# USB_POWER.net
KiCad netlist of a schematic drawn in Altium Designer
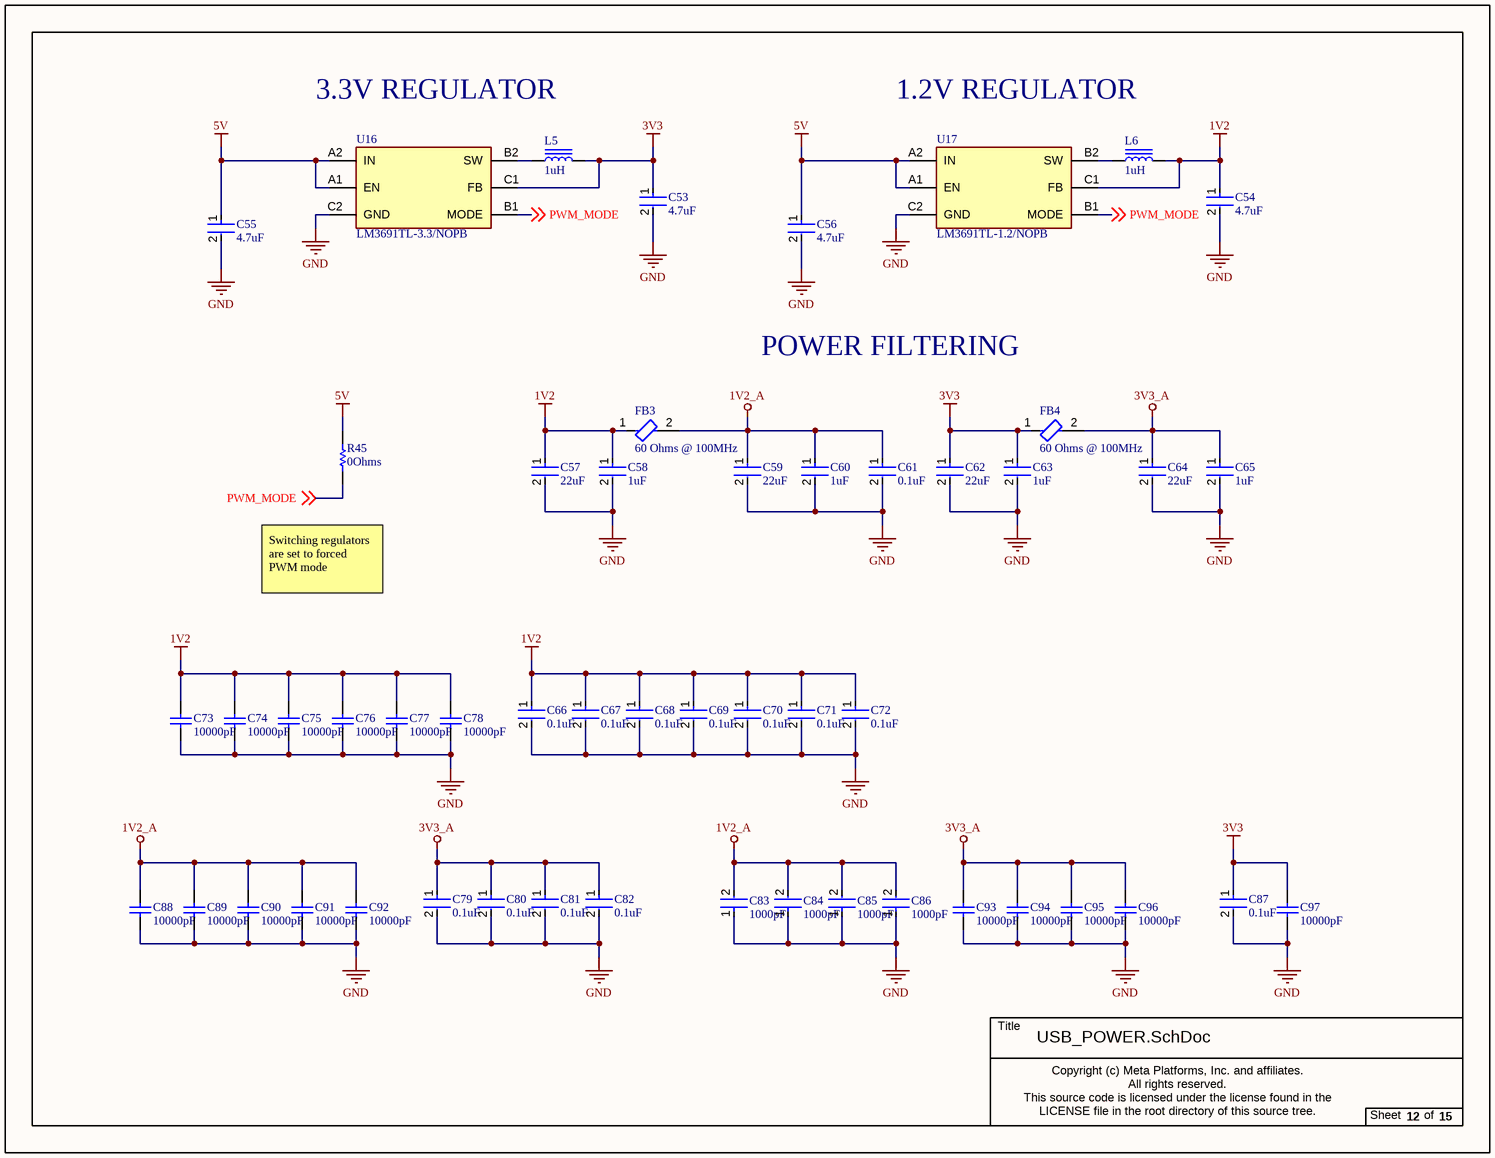
[diagram p0: USB_POWER.SchDoc]

(export (version "E")
  (design (tool "Eeschema 10.0.6"))
  (components
    (comp (ref "C53")
      (value "4.7uF")
      (footprint "FP-CL828-IPC_C")
      (description "Cap Ceramic 4.7uF 10V X5R ±10% SMD 0402 +85°C Paper T/R")
      (fields (field (name "TOLERANCE") "10%"))
      (libsource (lib "Altium Content Vault") (part "b4654b650e69147ec39a6b967a45e02"))
    )
    (comp (ref "C54")
      (value "4.7uF")
      (footprint "FP-CL828-IPC_C")
      (description "Cap Ceramic 4.7uF 10V X5R ±10% SMD 0402 +85°C Paper T/R")
      (fields (field (name "TOLERANCE") "10%"))
      (libsource (lib "Altium Content Vault") (part "b4654b650e69147ec39a6b967a45e02"))
    )
    (comp (ref "C55")
      (value "4.7uF")
      (footprint "FP-CL828-IPC_C")
      (description "Cap Ceramic 4.7uF 10V X5R ±10% SMD 0402 +85°C Paper T/R")
      (fields (field (name "TOLERANCE") "10%"))
      (libsource (lib "Altium Content Vault") (part "b4654b650e69147ec39a6b967a45e02"))
    )
    (comp (ref "C56")
      (value "4.7uF")
      (footprint "FP-CL828-IPC_C")
      (description "Cap Ceramic 4.7uF 10V X5R ±10% SMD 0402 +85°C Paper T/R")
      (fields (field (name "TOLERANCE") "10%"))
      (libsource (lib "Altium Content Vault") (part "b4654b650e69147ec39a6b967a45e02"))
    )
    (comp (ref "C57")
      (value "22uF")
      (footprint "FP-CL05A226MQ5N6J8-IPC_C")
      (description "CAP CER 22UF 6.3V X5R 0402")
      (fields
        (field (name "MANUFACTURER PART NUMBER") "CL05A226MQ5N6J8")
        (field (name "MANUFACTURER") "Samsung Electro-Mechanics")
      )
      (libsource (lib "Altium Content Vault") (part "11868f565c42a9108669ba33697ecf6"))
    )
    (comp (ref "C58")
      (value "1uF")
      (footprint "FP-CL511-IPC_C")
      (description "Cap Ceramic 1uF 10V X5R ±10% SMD 0402 +85°C Paper T/R")
      (fields (field (name "TOLERANCE") "10%"))
      (libsource (lib "Altium Content Vault") (part "b4654b650e69147ec39a6b967a45e02"))
    )
    (comp (ref "C59")
      (value "22uF")
      (footprint "FP-CL05A226MQ5N6J8-IPC_C")
      (description "CAP CER 22UF 6.3V X5R 0402")
      (fields
        (field (name "MANUFACTURER PART NUMBER") "CL05A226MQ5N6J8")
        (field (name "MANUFACTURER") "Samsung Electro-Mechanics")
      )
      (libsource (lib "Altium Content Vault") (part "11868f565c42a9108669ba33697ecf6"))
    )
    (comp (ref "C60")
      (value "1uF")
      (footprint "FP-CL511-IPC_C")
      (description "Cap Ceramic 1uF 10V X5R ±10% SMD 0402 +85°C Paper T/R")
      (fields (field (name "TOLERANCE") "10%"))
      (libsource (lib "Altium Content Vault") (part "b4654b650e69147ec39a6b967a45e02"))
    )
    (comp (ref "C61")
      (value "0.1uF")
      (footprint "FP-CC0201-BA-MFG")
      (description "CAP CER 0.1UF 6.3V X5R 0201")
      (fields (field (name "MANUFACTURER") "Yageo") (field (name "TOLERANCE") "0.1"))
      (libsource (lib "Altium Content Vault") (part "11868f565c42a9108669ba33697ecf6"))
    )
    (comp (ref "C62")
      (value "22uF")
      (footprint "FP-CL05A226MQ5N6J8-IPC_C")
      (description "CAP CER 22UF 6.3V X5R 0402")
      (fields
        (field (name "MANUFACTURER PART NUMBER") "CL05A226MQ5N6J8")
        (field (name "MANUFACTURER") "Samsung Electro-Mechanics")
      )
      (libsource (lib "Altium Content Vault") (part "11868f565c42a9108669ba33697ecf6"))
    )
    (comp (ref "C63")
      (value "1uF")
      (footprint "FP-CL511-IPC_C")
      (description "Cap Ceramic 1uF 10V X5R ±10% SMD 0402 +85°C Paper T/R")
      (fields (field (name "TOLERANCE") "10%"))
      (libsource (lib "Altium Content Vault") (part "b4654b650e69147ec39a6b967a45e02"))
    )
    (comp (ref "C64")
      (value "22uF")
      (footprint "FP-CL05A226MQ5N6J8-IPC_C")
      (description "CAP CER 22UF 6.3V X5R 0402")
      (fields
        (field (name "MANUFACTURER PART NUMBER") "CL05A226MQ5N6J8")
        (field (name "MANUFACTURER") "Samsung Electro-Mechanics")
      )
      (libsource (lib "Altium Content Vault") (part "11868f565c42a9108669ba33697ecf6"))
    )
    (comp (ref "C65")
      (value "1uF")
      (footprint "FP-CL511-IPC_C")
      (description "Cap Ceramic 1uF 10V X5R ±10% SMD 0402 +85°C Paper T/R")
      (fields (field (name "TOLERANCE") "10%"))
      (libsource (lib "Altium Content Vault") (part "b4654b650e69147ec39a6b967a45e02"))
    )
    (comp (ref "C66")
      (value "0.1uF")
      (footprint "FP-CC0201-BA-MFG")
      (description "CAP CER 0.1UF 6.3V X5R 0201")
      (fields (field (name "MANUFACTURER") "Yageo") (field (name "TOLERANCE") "0.1"))
      (libsource (lib "Altium Content Vault") (part "11868f565c42a9108669ba33697ecf6"))
    )
    (comp (ref "C67")
      (value "0.1uF")
      (footprint "FP-CC0201-BA-MFG")
      (description "CAP CER 0.1UF 6.3V X5R 0201")
      (fields (field (name "MANUFACTURER") "Yageo") (field (name "TOLERANCE") "0.1"))
      (libsource (lib "Altium Content Vault") (part "11868f565c42a9108669ba33697ecf6"))
    )
    (comp (ref "C68")
      (value "0.1uF")
      (footprint "FP-CC0201-BA-MFG")
      (description "CAP CER 0.1UF 6.3V X5R 0201")
      (fields (field (name "MANUFACTURER") "Yageo") (field (name "TOLERANCE") "0.1"))
      (libsource (lib "Altium Content Vault") (part "11868f565c42a9108669ba33697ecf6"))
    )
    (comp (ref "C69")
      (value "0.1uF")
      (footprint "FP-CC0201-BA-MFG")
      (description "CAP CER 0.1UF 6.3V X5R 0201")
      (fields (field (name "MANUFACTURER") "Yageo") (field (name "TOLERANCE") "0.1"))
      (libsource (lib "Altium Content Vault") (part "11868f565c42a9108669ba33697ecf6"))
    )
    (comp (ref "C70")
      (value "0.1uF")
      (footprint "FP-CC0201-BA-MFG")
      (description "CAP CER 0.1UF 6.3V X5R 0201")
      (fields (field (name "MANUFACTURER") "Yageo") (field (name "TOLERANCE") "0.1"))
      (libsource (lib "Altium Content Vault") (part "11868f565c42a9108669ba33697ecf6"))
    )
    (comp (ref "C71")
      (value "0.1uF")
      (footprint "FP-CC0201-BA-MFG")
      (description "CAP CER 0.1UF 6.3V X5R 0201")
      (fields (field (name "MANUFACTURER") "Yageo") (field (name "TOLERANCE") "0.1"))
      (libsource (lib "Altium Content Vault") (part "11868f565c42a9108669ba33697ecf6"))
    )
    (comp (ref "C72")
      (value "0.1uF")
      (footprint "FP-CC0201-BA-MFG")
      (description "CAP CER 0.1UF 6.3V X5R 0201")
      (fields (field (name "MANUFACTURER") "Yageo") (field (name "TOLERANCE") "0.1"))
      (libsource (lib "Altium Content Vault") (part "11868f565c42a9108669ba33697ecf6"))
    )
    (comp (ref "C73")
      (value "10000pF")
      (footprint "CAPC1005X55X25LL05T10")
      (fields (field (name "MANUFACTURER") "Murata") (field (name "PART NUMBER") "GRM155R71E103KA01D"))
      (libsource (lib "Altium Content Vault") (part "CAP"))
    )
    (comp (ref "C74")
      (value "10000pF")
      (footprint "CAPC1005X55X25LL05T10")
      (fields (field (name "MANUFACTURER") "Murata") (field (name "PART NUMBER") "GRM155R71E103KA01D"))
      (libsource (lib "Altium Content Vault") (part "CAP"))
    )
    (comp (ref "C75")
      (value "10000pF")
      (footprint "CAPC1005X55X25LL05T10")
      (fields (field (name "MANUFACTURER") "Murata") (field (name "PART NUMBER") "GRM155R71E103KA01D"))
      (libsource (lib "Altium Content Vault") (part "CAP"))
    )
    (comp (ref "C76")
      (value "10000pF")
      (footprint "CAPC1005X55X25LL05T10")
      (fields (field (name "MANUFACTURER") "Murata") (field (name "PART NUMBER") "GRM155R71E103KA01D"))
      (libsource (lib "Altium Content Vault") (part "CAP"))
    )
    (comp (ref "C77")
      (value "10000pF")
      (footprint "CAPC1005X55X25LL05T10")
      (fields (field (name "MANUFACTURER") "Murata") (field (name "PART NUMBER") "GRM155R71E103KA01D"))
      (libsource (lib "Altium Content Vault") (part "CAP"))
    )
    (comp (ref "C78")
      (value "10000pF")
      (footprint "CAPC1005X55X25LL05T10")
      (fields (field (name "MANUFACTURER") "Murata") (field (name "PART NUMBER") "GRM155R71E103KA01D"))
      (libsource (lib "Altium Content Vault") (part "CAP"))
    )
    (comp (ref "C79")
      (value "0.1uF")
      (footprint "FP-CC0201-BA-MFG")
      (description "CAP CER 0.1UF 6.3V X5R 0201")
      (fields (field (name "MANUFACTURER") "Yageo") (field (name "TOLERANCE") "0.1"))
      (libsource (lib "Altium Content Vault") (part "11868f565c42a9108669ba33697ecf6"))
    )
    (comp (ref "C80")
      (value "0.1uF")
      (footprint "FP-CC0201-BA-MFG")
      (description "CAP CER 0.1UF 6.3V X5R 0201")
      (fields (field (name "MANUFACTURER") "Yageo") (field (name "TOLERANCE") "0.1"))
      (libsource (lib "Altium Content Vault") (part "11868f565c42a9108669ba33697ecf6"))
    )
    (comp (ref "C81")
      (value "0.1uF")
      (footprint "FP-CC0201-BA-MFG")
      (description "CAP CER 0.1UF 6.3V X5R 0201")
      (fields (field (name "MANUFACTURER") "Yageo") (field (name "TOLERANCE") "0.1"))
      (libsource (lib "Altium Content Vault") (part "11868f565c42a9108669ba33697ecf6"))
    )
    (comp (ref "C82")
      (value "0.1uF")
      (footprint "FP-CC0201-BA-MFG")
      (description "CAP CER 0.1UF 6.3V X5R 0201")
      (fields (field (name "MANUFACTURER") "Yageo") (field (name "TOLERANCE") "0.1"))
      (libsource (lib "Altium Content Vault") (part "11868f565c42a9108669ba33697ecf6"))
    )
    (comp (ref "C83")
      (value "1000pF")
      (footprint "FP-C0402-BB-MFG")
      (description "Cap Ceramic 0.001uF 50V X7R 10% SMD 0402 125°C Paper T/R (Alt: C0402C102K5RACTU)")
      (fields
        (field (name "OCTOPART") "https://octopart.com/c0402c102k5ractu-kemet-100678")
        (field (name "TOLERANCE") "0.1")
      )
      (libsource (lib "Altium Content Vault") (part "b4654b650e69147ec39a6b967a45e02"))
    )
    (comp (ref "C84")
      (value "1000pF")
      (footprint "FP-C0402-BB-MFG")
      (description "Cap Ceramic 0.001uF 50V X7R 10% SMD 0402 125°C Paper T/R (Alt: C0402C102K5RACTU)")
      (fields
        (field (name "OCTOPART") "https://octopart.com/c0402c102k5ractu-kemet-100678")
        (field (name "TOLERANCE") "0.1")
      )
      (libsource (lib "Altium Content Vault") (part "b4654b650e69147ec39a6b967a45e02"))
    )
    (comp (ref "C85")
      (value "1000pF")
      (footprint "FP-C0402-BB-MFG")
      (description "Cap Ceramic 0.001uF 50V X7R 10% SMD 0402 125°C Paper T/R (Alt: C0402C102K5RACTU)")
      (fields
        (field (name "OCTOPART") "https://octopart.com/c0402c102k5ractu-kemet-100678")
        (field (name "TOLERANCE") "0.1")
      )
      (libsource (lib "Altium Content Vault") (part "b4654b650e69147ec39a6b967a45e02"))
    )
    (comp (ref "C86")
      (value "1000pF")
      (footprint "FP-C0402-BB-MFG")
      (description "Cap Ceramic 0.001uF 50V X7R 10% SMD 0402 125°C Paper T/R (Alt: C0402C102K5RACTU)")
      (fields
        (field (name "OCTOPART") "https://octopart.com/c0402c102k5ractu-kemet-100678")
        (field (name "TOLERANCE") "0.1")
      )
      (libsource (lib "Altium Content Vault") (part "b4654b650e69147ec39a6b967a45e02"))
    )
    (comp (ref "C87")
      (value "0.1uF")
      (footprint "FP-CC0201-BA-MFG")
      (description "CAP CER 0.1UF 6.3V X5R 0201")
      (fields (field (name "MANUFACTURER") "Yageo") (field (name "TOLERANCE") "0.1"))
      (libsource (lib "Altium Content Vault") (part "11868f565c42a9108669ba33697ecf6"))
    )
    (comp (ref "C88")
      (value "10000pF")
      (footprint "CAPC1005X55X25LL05T10")
      (fields (field (name "MANUFACTURER") "Murata") (field (name "PART NUMBER") "GRM155R71E103KA01D"))
      (libsource (lib "Altium Content Vault") (part "CAP"))
    )
    (comp (ref "C89")
      (value "10000pF")
      (footprint "CAPC1005X55X25LL05T10")
      (fields (field (name "MANUFACTURER") "Murata") (field (name "PART NUMBER") "GRM155R71E103KA01D"))
      (libsource (lib "Altium Content Vault") (part "CAP"))
    )
    (comp (ref "C90")
      (value "10000pF")
      (footprint "CAPC1005X55X25LL05T10")
      (fields (field (name "MANUFACTURER") "Murata") (field (name "PART NUMBER") "GRM155R71E103KA01D"))
      (libsource (lib "Altium Content Vault") (part "CAP"))
    )
    (comp (ref "C91")
      (value "10000pF")
      (footprint "CAPC1005X55X25LL05T10")
      (fields (field (name "MANUFACTURER") "Murata") (field (name "PART NUMBER") "GRM155R71E103KA01D"))
      (libsource (lib "Altium Content Vault") (part "CAP"))
    )
    (comp (ref "C92")
      (value "10000pF")
      (footprint "CAPC1005X55X25LL05T10")
      (fields (field (name "MANUFACTURER") "Murata") (field (name "PART NUMBER") "GRM155R71E103KA01D"))
      (libsource (lib "Altium Content Vault") (part "CAP"))
    )
    (comp (ref "C93")
      (value "10000pF")
      (footprint "CAPC1005X55X25LL05T10")
      (fields (field (name "MANUFACTURER") "Murata") (field (name "PART NUMBER") "GRM155R71E103KA01D"))
      (libsource (lib "Altium Content Vault") (part "CAP"))
    )
    (comp (ref "C94")
      (value "10000pF")
      (footprint "CAPC1005X55X25LL05T10")
      (fields (field (name "MANUFACTURER") "Murata") (field (name "PART NUMBER") "GRM155R71E103KA01D"))
      (libsource (lib "Altium Content Vault") (part "CAP"))
    )
    (comp (ref "C95")
      (value "10000pF")
      (footprint "CAPC1005X55X25LL05T10")
      (fields (field (name "MANUFACTURER") "Murata") (field (name "PART NUMBER") "GRM155R71E103KA01D"))
      (libsource (lib "Altium Content Vault") (part "CAP"))
    )
    (comp (ref "C96")
      (value "10000pF")
      (footprint "CAPC1005X55X25LL05T10")
      (fields (field (name "MANUFACTURER") "Murata") (field (name "PART NUMBER") "GRM155R71E103KA01D"))
      (libsource (lib "Altium Content Vault") (part "CAP"))
    )
    (comp (ref "C97")
      (value "10000pF")
      (footprint "CAPC1005X55X25LL05T10")
      (fields (field (name "MANUFACTURER") "Murata") (field (name "PART NUMBER") "GRM155R71E103KA01D"))
      (libsource (lib "Altium Content Vault") (part "CAP"))
    )
    (comp (ref "FB3")
      (value "60 Ohms @ 100MHz")
      (footprint "FP-BLM15-0_05-d0_7-IPC_B")
      (description "Chip Ferrite Bead, 0402, 60Ω @ 100MHz, 0.06Ω, 25%, 1.7A")
      (fields (field (name "TOLERANCE") "25%"))
      (libsource (lib "Altium Content Vault") (part "5f30dd21d616792df468990f7003faa"))
    )
    (comp (ref "FB4")
      (value "60 Ohms @ 100MHz")
      (footprint "FP-BLM15-0_05-d0_7-IPC_B")
      (description "Chip Ferrite Bead, 0402, 60Ω @ 100MHz, 0.06Ω, 25%, 1.7A")
      (fields (field (name "TOLERANCE") "25%"))
      (libsource (lib "Altium Content Vault") (part "5f30dd21d616792df468990f7003faa"))
    )
    (comp (ref "L5")
      (value "1uH")
      (footprint "IND 0603_1608 RF WW")
      (description "SMT Inductor")
      (fields (field (name "MANUFACTURER") "Taiyo Yuden") (field (name "PART NUMBER") "MCHK1608T1R0MKN"))
      (libsource (lib "Phalanx") (part "MCHK1608T1R0MKN"))
    )
    (comp (ref "L6")
      (value "1uH")
      (footprint "IND 0603_1608 RF WW")
      (description "SMT Inductor")
      (fields (field (name "MANUFACTURER") "Taiyo Yuden") (field (name "PART NUMBER") "MCHK1608T1R0MKN"))
      (libsource (lib "Phalanx") (part "MCHK1608T1R0MKN"))
    )
    (comp (ref "R45")
      (value "0Ohms")
      (footprint "RESC1005X40X25ML05T10")
      (fields (field (name "PART NUMBER") "CRCW040210K0FKEDHP") (field (name "MANUFACTURER") "Vishay Dale"))
      (libsource (lib "Altium Content Vault") (part "RES"))
    )
    (comp (ref "U16")
      (value "LM3691TL-3.3/NOPB")
      (footprint "YZR0006APAF")
      (description "Buck Switching Regulator IC Positive Fixed 3.3V 1 Output 1A 6-WFBGA, DSBGA")
      (fields
        (field (name "MANUFACTURER") "Texas Instruments")
        (field (name "PART NUMBER") "LM3691TL-3.3/NOPB")
      )
      (libsource (lib "Phalanx") (part "LM3691TL-3.3/NOPB"))
    )
    (comp (ref "U17")
      (value "LM3691TL-1.2/NOPB")
      (footprint "YZR0006APAF")
      (description "Buck Switching Regulator IC Positive Fixed 1.2V 1 Output 1A 6-WFBGA, DSBGA")
      (fields
        (field (name "MANUFACTURER") "Texas Instruments")
        (field (name "PART NUMBER") "LM3691TL-1.2/NOPB")
      )
      (libsource (lib "Phalanx") (part "LM3691TL-1.2/NOPB"))
    )
  )
  (nets
    (net (code "1") (name "1V2") (class "Default")
      (node (ref "C54") (pin "1") (pinfunction "1_1") (pintype "passive"))
      (node (ref "C57") (pin "1") (pinfunction "1_1") (pintype "passive"))
      (node (ref "C58") (pin "1") (pinfunction "1_1") (pintype "passive"))
      (node (ref "C66") (pin "1") (pinfunction "1_1") (pintype "passive"))
      (node (ref "C67") (pin "1") (pinfunction "1_1") (pintype "passive"))
      (node (ref "C68") (pin "1") (pinfunction "1_1") (pintype "passive"))
      (node (ref "C69") (pin "1") (pinfunction "1_1") (pintype "passive"))
      (node (ref "C70") (pin "1") (pinfunction "1_1") (pintype "passive"))
      (node (ref "C71") (pin "1") (pinfunction "1_1") (pintype "passive"))
      (node (ref "C72") (pin "1") (pinfunction "1_1") (pintype "passive"))
      (node (ref "C73") (pin "2") (pinfunction "2_2") (pintype "passive"))
      (node (ref "C74") (pin "2") (pinfunction "2_2") (pintype "passive"))
      (node (ref "C75") (pin "2") (pinfunction "2_2") (pintype "passive"))
      (node (ref "C76") (pin "2") (pinfunction "2_2") (pintype "passive"))
      (node (ref "C77") (pin "2") (pinfunction "2_2") (pintype "passive"))
      (node (ref "C78") (pin "2") (pinfunction "2_2") (pintype "passive"))
      (node (ref "FB3") (pin "1") (pinfunction "1_1") (pintype "passive"))
      (node (ref "L6") (pin "2") (pinfunction "2_2") (pintype "passive"))
      (node (ref "U17") (pin "C1") (pinfunction "FB_C1") (pintype "passive"))
    )
    (net (code "2") (name "1V2_A") (class "Default")
      (node (ref "C59") (pin "1") (pinfunction "1_1") (pintype "passive"))
      (node (ref "C60") (pin "1") (pinfunction "1_1") (pintype "passive"))
      (node (ref "C61") (pin "1") (pinfunction "1_1") (pintype "passive"))
      (node (ref "C83") (pin "2") (pinfunction "2_2") (pintype "passive"))
      (node (ref "C84") (pin "2") (pinfunction "2_2") (pintype "passive"))
      (node (ref "C85") (pin "2") (pinfunction "2_2") (pintype "passive"))
      (node (ref "C86") (pin "2") (pinfunction "2_2") (pintype "passive"))
      (node (ref "C88") (pin "2") (pinfunction "2_2") (pintype "passive"))
      (node (ref "C89") (pin "2") (pinfunction "2_2") (pintype "passive"))
      (node (ref "C90") (pin "2") (pinfunction "2_2") (pintype "passive"))
      (node (ref "C91") (pin "2") (pinfunction "2_2") (pintype "passive"))
      (node (ref "C92") (pin "2") (pinfunction "2_2") (pintype "passive"))
      (node (ref "FB3") (pin "2") (pinfunction "2_2") (pintype "passive"))
    )
    (net (code "3") (name "3V3") (class "Default")
      (node (ref "C53") (pin "1") (pinfunction "1_1") (pintype "passive"))
      (node (ref "C62") (pin "1") (pinfunction "1_1") (pintype "passive"))
      (node (ref "C63") (pin "1") (pinfunction "1_1") (pintype "passive"))
      (node (ref "C87") (pin "1") (pinfunction "1_1") (pintype "passive"))
      (node (ref "C97") (pin "2") (pinfunction "2_2") (pintype "passive"))
      (node (ref "FB4") (pin "1") (pinfunction "1_1") (pintype "passive"))
      (node (ref "L5") (pin "2") (pinfunction "2_2") (pintype "passive"))
      (node (ref "U16") (pin "C1") (pinfunction "FB_C1") (pintype "passive"))
    )
    (net (code "4") (name "3V3_A") (class "Default")
      (node (ref "C64") (pin "1") (pinfunction "1_1") (pintype "passive"))
      (node (ref "C65") (pin "1") (pinfunction "1_1") (pintype "passive"))
      (node (ref "C79") (pin "1") (pinfunction "1_1") (pintype "passive"))
      (node (ref "C80") (pin "1") (pinfunction "1_1") (pintype "passive"))
      (node (ref "C81") (pin "1") (pinfunction "1_1") (pintype "passive"))
      (node (ref "C82") (pin "1") (pinfunction "1_1") (pintype "passive"))
      (node (ref "C93") (pin "2") (pinfunction "2_2") (pintype "passive"))
      (node (ref "C94") (pin "2") (pinfunction "2_2") (pintype "passive"))
      (node (ref "C95") (pin "2") (pinfunction "2_2") (pintype "passive"))
      (node (ref "C96") (pin "2") (pinfunction "2_2") (pintype "passive"))
      (node (ref "FB4") (pin "2") (pinfunction "2_2") (pintype "passive"))
    )
    (net (code "5") (name "5V") (class "Default")
      (node (ref "C55") (pin "1") (pinfunction "1_1") (pintype "passive"))
      (node (ref "C56") (pin "1") (pinfunction "1_1") (pintype "passive"))
      (node (ref "R45") (pin "1") (pinfunction "1_1") (pintype "passive"))
      (node (ref "U16") (pin "A1") (pinfunction "EN_A1") (pintype "passive"))
      (node (ref "U16") (pin "A2") (pinfunction "IN_A2") (pintype "passive"))
      (node (ref "U17") (pin "A1") (pinfunction "EN_A1") (pintype "passive"))
      (node (ref "U17") (pin "A2") (pinfunction "IN_A2") (pintype "passive"))
    )
    (net (code "6") (name "GND") (class "Default")
      (node (ref "C53") (pin "2") (pinfunction "2_2") (pintype "passive"))
      (node (ref "C54") (pin "2") (pinfunction "2_2") (pintype "passive"))
      (node (ref "C55") (pin "2") (pinfunction "2_2") (pintype "passive"))
      (node (ref "C56") (pin "2") (pinfunction "2_2") (pintype "passive"))
      (node (ref "C57") (pin "2") (pinfunction "2_2") (pintype "passive"))
      (node (ref "C58") (pin "2") (pinfunction "2_2") (pintype "passive"))
      (node (ref "C59") (pin "2") (pinfunction "2_2") (pintype "passive"))
      (node (ref "C60") (pin "2") (pinfunction "2_2") (pintype "passive"))
      (node (ref "C61") (pin "2") (pinfunction "2_2") (pintype "passive"))
      (node (ref "C62") (pin "2") (pinfunction "2_2") (pintype "passive"))
      (node (ref "C63") (pin "2") (pinfunction "2_2") (pintype "passive"))
      (node (ref "C64") (pin "2") (pinfunction "2_2") (pintype "passive"))
      (node (ref "C65") (pin "2") (pinfunction "2_2") (pintype "passive"))
      (node (ref "C66") (pin "2") (pinfunction "2_2") (pintype "passive"))
      (node (ref "C67") (pin "2") (pinfunction "2_2") (pintype "passive"))
      (node (ref "C68") (pin "2") (pinfunction "2_2") (pintype "passive"))
      (node (ref "C69") (pin "2") (pinfunction "2_2") (pintype "passive"))
      (node (ref "C70") (pin "2") (pinfunction "2_2") (pintype "passive"))
      (node (ref "C71") (pin "2") (pinfunction "2_2") (pintype "passive"))
      (node (ref "C72") (pin "2") (pinfunction "2_2") (pintype "passive"))
      (node (ref "C73") (pin "1") (pinfunction "1_1") (pintype "passive"))
      (node (ref "C74") (pin "1") (pinfunction "1_1") (pintype "passive"))
      (node (ref "C75") (pin "1") (pinfunction "1_1") (pintype "passive"))
      (node (ref "C76") (pin "1") (pinfunction "1_1") (pintype "passive"))
      (node (ref "C77") (pin "1") (pinfunction "1_1") (pintype "passive"))
      (node (ref "C78") (pin "1") (pinfunction "1_1") (pintype "passive"))
      (node (ref "C79") (pin "2") (pinfunction "2_2") (pintype "passive"))
      (node (ref "C80") (pin "2") (pinfunction "2_2") (pintype "passive"))
      (node (ref "C81") (pin "2") (pinfunction "2_2") (pintype "passive"))
      (node (ref "C82") (pin "2") (pinfunction "2_2") (pintype "passive"))
      (node (ref "C83") (pin "1") (pinfunction "1_1") (pintype "passive"))
      (node (ref "C84") (pin "1") (pinfunction "1_1") (pintype "passive"))
      (node (ref "C85") (pin "1") (pinfunction "1_1") (pintype "passive"))
      (node (ref "C86") (pin "1") (pinfunction "1_1") (pintype "passive"))
      (node (ref "C87") (pin "2") (pinfunction "2_2") (pintype "passive"))
      (node (ref "C88") (pin "1") (pinfunction "1_1") (pintype "passive"))
      (node (ref "C89") (pin "1") (pinfunction "1_1") (pintype "passive"))
      (node (ref "C90") (pin "1") (pinfunction "1_1") (pintype "passive"))
      (node (ref "C91") (pin "1") (pinfunction "1_1") (pintype "passive"))
      (node (ref "C92") (pin "1") (pinfunction "1_1") (pintype "passive"))
      (node (ref "C93") (pin "1") (pinfunction "1_1") (pintype "passive"))
      (node (ref "C94") (pin "1") (pinfunction "1_1") (pintype "passive"))
      (node (ref "C95") (pin "1") (pinfunction "1_1") (pintype "passive"))
      (node (ref "C96") (pin "1") (pinfunction "1_1") (pintype "passive"))
      (node (ref "C97") (pin "1") (pinfunction "1_1") (pintype "passive"))
      (node (ref "U16") (pin "C2") (pinfunction "GND_C2") (pintype "passive"))
      (node (ref "U17") (pin "C2") (pinfunction "GND_C2") (pintype "passive"))
    )
    (net (code "7") (name "Net-(U16-SW)") (class "Default")
      (node (ref "L5") (pin "1") (pinfunction "1_1") (pintype "passive"))
      (node (ref "U16") (pin "B2") (pinfunction "SW_B2") (pintype "passive"))
    )
    (net (code "8") (name "Net-(U17-SW)") (class "Default")
      (node (ref "L6") (pin "1") (pinfunction "1_1") (pintype "passive"))
      (node (ref "U17") (pin "B2") (pinfunction "SW_B2") (pintype "passive"))
    )
    (net (code "9") (name "PWM_MODE") (class "Default")
      (node (ref "R45") (pin "2") (pinfunction "2_2") (pintype "passive"))
      (node (ref "U16") (pin "B1") (pinfunction "MODE_B1") (pintype "passive"))
      (node (ref "U17") (pin "B1") (pinfunction "MODE_B1") (pintype "passive"))
    )
  )
)
